# p2c14_001.net
KiCad netlist of a schematic drawn in EAGLE
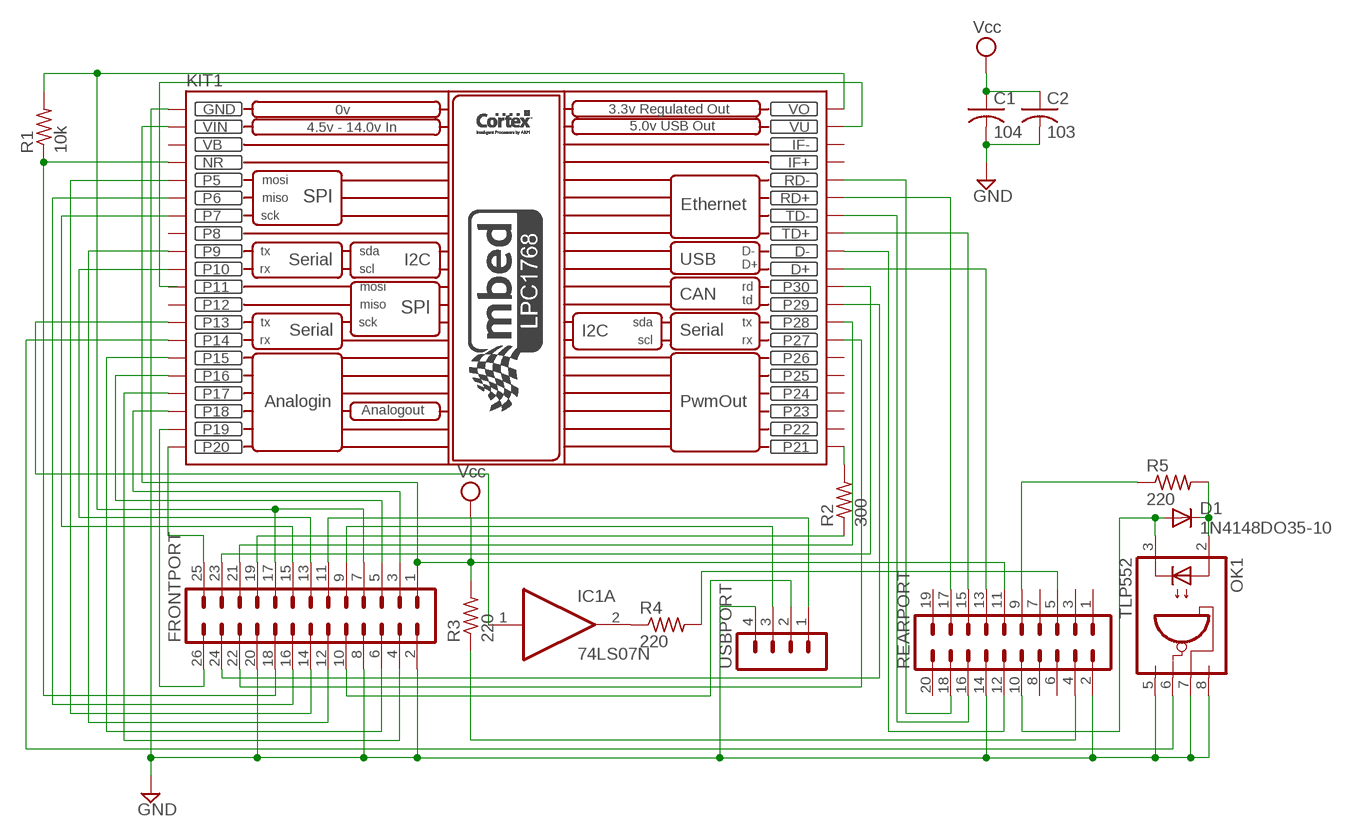
[diagram p0: schematic, sheet 1]

(export (version "E")
  (design (tool "Eeschema 10.0.6"))
  (components
    (comp (ref "C1")
      (value "104")
      (footprint "eagle-import:C025-025X050")
      (libsource (lib "eagle-import") (part "C-US025-025X050"))
    )
    (comp (ref "C2")
      (value "103")
      (footprint "eagle-import:C050-075X075")
      (libsource (lib "eagle-import") (part "C-US050-075X075"))
    )
    (comp (ref "D1")
      (value "1N4148DO35-10")
      (footprint "eagle-import:DO35-10")
      (libsource (lib "eagle-import") (part "1N4148DO35-10"))
    )
    (comp (ref "FRONTPORT")
      (value "ML26L")
      (footprint "eagle-import:ML26L")
      (libsource (lib "eagle-import") (part "ML26L"))
    )
    (comp (ref "IC1")
      (value "74LS07N")
      (footprint "eagle-import:DIL14")
      (libsource (lib "eagle-import") (part "7407NLS"))
    )
    (comp (ref "KIT1")
      (value "MBED_NXP_LPC1768")
      (footprint "eagle-import:MBED-KIT")
      (libsource (lib "eagle-import") (part "MBED_NXP_LPC1768"))
    )
    (comp (ref "OK1")
      (value "TLP552")
      (footprint "eagle-import:DIL08")
      (fields (field (name "MPN") "6N137"))
      (libsource (lib "eagle-import") (part "6N137"))
    )
    (comp (ref "R1")
      (value "10k")
      (footprint "eagle-import:0204_7")
      (libsource (lib "eagle-import") (part "R-US_0204/7"))
    )
    (comp (ref "R2")
      (value "300")
      (footprint "eagle-import:0204_7")
      (libsource (lib "eagle-import") (part "R-US_0204/7"))
    )
    (comp (ref "R3")
      (value "220")
      (footprint "eagle-import:0204_7")
      (libsource (lib "eagle-import") (part "R-US_0204/7"))
    )
    (comp (ref "R4")
      (value "220")
      (footprint "eagle-import:0204_7")
      (libsource (lib "eagle-import") (part "R-US_0204/7"))
    )
    (comp (ref "R5")
      (value "220")
      (footprint "eagle-import:0204_7")
      (libsource (lib "eagle-import") (part "R-US_0204/7"))
    )
    (comp (ref "REARPORT")
      (value "ML20L")
      (footprint "eagle-import:ML20L")
      (libsource (lib "eagle-import") (part "ML20L"))
    )
    (comp (ref "USBPORT")
      (value "MA04-1")
      (footprint "eagle-import:MA04-1")
      (libsource (lib "eagle-import") (part "MA04-1"))
    )
  )
  (nets
    (net (code "1") (name "/VB") (class "Default")
      (node (ref "KIT1") (pin "VB") (pinfunction "VB_VB") (pintype "power_in"))
    )
    (net (code "2") (name "GND") (class "Default")
      (node (ref "C1") (pin "2") (pinfunction "2_2") (pintype "passive"))
      (node (ref "C2") (pin "2") (pinfunction "2_2") (pintype "passive"))
      (node (ref "FRONTPORT") (pin "2") (pinfunction "2_2") (pintype "passive"))
      (node (ref "FRONTPORT") (pin "20") (pinfunction "20_20") (pintype "passive"))
      (node (ref "FRONTPORT") (pin "8") (pinfunction "8_8") (pintype "passive"))
      (node (ref "KIT1") (pin "GND") (pinfunction "GND_GND") (pintype "power_in"))
      (node (ref "OK1") (pin "5") (pinfunction "GND_5") (pintype "passive"))
      (node (ref "OK1") (pin "7") (pinfunction "VE_7") (pintype "passive"))
      (node (ref "OK1") (pin "8") (pinfunction "VCC_8") (pintype "passive"))
      (node (ref "REARPORT") (pin "14") (pinfunction "14_14") (pintype "passive"))
      (node (ref "REARPORT") (pin "2") (pinfunction "2_2") (pintype "passive"))
      (node (ref "USBPORT") (pin "4") (pinfunction "4_4") (pintype "passive"))
    )
    (net (code "3") (name "Net-(FRONTPORT-Pad9)") (class "Default")
      (node (ref "FRONTPORT") (pin "9") (pinfunction "9_9") (pintype "passive"))
      (node (ref "USBPORT") (pin "3") (pinfunction "3_3") (pintype "passive"))
    )
    (net (code "4") (name "Net-(FRONTPORT-Pad10)") (class "Default")
      (node (ref "FRONTPORT") (pin "10") (pinfunction "10_10") (pintype "passive"))
      (node (ref "USBPORT") (pin "2") (pinfunction "2_2") (pintype "passive"))
    )
    (net (code "5") (name "Net-(FRONTPORT-Pad11)") (class "Default")
      (node (ref "FRONTPORT") (pin "11") (pinfunction "11_11") (pintype "passive"))
      (node (ref "USBPORT") (pin "1") (pinfunction "1_1") (pintype "passive"))
    )
    (net (code "6") (name "Net-(FRONTPORT-Pad18)") (class "Default")
      (node (ref "FRONTPORT") (pin "18") (pinfunction "18_18") (pintype "passive"))
      (node (ref "KIT1") (pin "NR") (pinfunction "NR_NR") (pintype "power_in"))
      (node (ref "R1") (pin "1") (pinfunction "1_1") (pintype "passive"))
    )
    (net (code "7") (name "Net-(FRONTPORT-Pad19)") (class "Default")
      (node (ref "FRONTPORT") (pin "19") (pinfunction "19_19") (pintype "passive"))
      (node (ref "R2") (pin "1") (pinfunction "1_1") (pintype "passive"))
    )
    (net (code "8") (name "Net-(IC1A-I)") (class "Default")
      (node (ref "IC1") (pin "1") (pinfunction "I_1") (pintype "input"))
      (node (ref "KIT1") (pin "P$13") (pinfunction "P13_P$13") (pintype "bidirectional"))
    )
    (net (code "9") (name "Net-(IC1A-O)") (class "Default")
      (node (ref "IC1") (pin "2") (pinfunction "O_2") (pintype "open_collector"))
      (node (ref "R4") (pin "1") (pinfunction "1_1") (pintype "passive"))
    )
    (net (code "10") (name "Net-(KIT1-P5)") (class "Default")
      (node (ref "FRONTPORT") (pin "14") (pinfunction "14_14") (pintype "passive"))
      (node (ref "KIT1") (pin "P$5") (pinfunction "P5_P$5") (pintype "bidirectional"))
    )
    (net (code "11") (name "Net-(KIT1-P6)") (class "Default")
      (node (ref "FRONTPORT") (pin "16") (pinfunction "16_16") (pintype "passive"))
      (node (ref "KIT1") (pin "P$6") (pinfunction "P6_P$6") (pintype "bidirectional"))
    )
    (net (code "12") (name "Net-(KIT1-P7)") (class "Default")
      (node (ref "FRONTPORT") (pin "15") (pinfunction "15_15") (pintype "passive"))
      (node (ref "KIT1") (pin "P$7") (pinfunction "P7_P$7") (pintype "bidirectional"))
    )
    (net (code "13") (name "Net-(KIT1-P9)") (class "Default")
      (node (ref "FRONTPORT") (pin "12") (pinfunction "12_12") (pintype "passive"))
      (node (ref "KIT1") (pin "P$9") (pinfunction "P9_P$9") (pintype "bidirectional"))
    )
    (net (code "14") (name "Net-(KIT1-P10)") (class "Default")
      (node (ref "FRONTPORT") (pin "13") (pinfunction "13_13") (pintype "passive"))
      (node (ref "KIT1") (pin "P$10") (pinfunction "P10_P$10") (pintype "bidirectional"))
    )
    (net (code "15") (name "Net-(KIT1-P14)") (class "Default")
      (node (ref "KIT1") (pin "P$14") (pinfunction "P14_P$14") (pintype "bidirectional"))
      (node (ref "OK1") (pin "6") (pinfunction "VO_6") (pintype "passive"))
    )
    (net (code "16") (name "Net-(KIT1-P15)") (class "Default")
      (node (ref "FRONTPORT") (pin "6") (pinfunction "6_6") (pintype "passive"))
      (node (ref "KIT1") (pin "P$15") (pinfunction "P15_P$15") (pintype "bidirectional"))
    )
    (net (code "17") (name "Net-(KIT1-P16)") (class "Default")
      (node (ref "FRONTPORT") (pin "5") (pinfunction "5_5") (pintype "passive"))
      (node (ref "KIT1") (pin "P$16") (pinfunction "P16_P$16") (pintype "bidirectional"))
    )
    (net (code "18") (name "Net-(KIT1-P17)") (class "Default")
      (node (ref "FRONTPORT") (pin "4") (pinfunction "4_4") (pintype "passive"))
      (node (ref "KIT1") (pin "P$17") (pinfunction "P17_P$17") (pintype "bidirectional"))
    )
    (net (code "19") (name "Net-(KIT1-P18)") (class "Default")
      (node (ref "FRONTPORT") (pin "3") (pinfunction "3_3") (pintype "passive"))
      (node (ref "KIT1") (pin "P$18") (pinfunction "P18_P$18") (pintype "bidirectional"))
    )
    (net (code "20") (name "Net-(KIT1-P19)") (class "Default")
      (node (ref "FRONTPORT") (pin "26") (pinfunction "26_26") (pintype "passive"))
      (node (ref "KIT1") (pin "P$19") (pinfunction "P19_P$19") (pintype "bidirectional"))
    )
    (net (code "21") (name "Net-(KIT1-P20)") (class "Default")
      (node (ref "FRONTPORT") (pin "25") (pinfunction "25_25") (pintype "passive"))
      (node (ref "KIT1") (pin "P$20") (pinfunction "P20_P$20") (pintype "bidirectional"))
    )
    (net (code "22") (name "Net-(KIT1-P21)") (class "Default")
      (node (ref "KIT1") (pin "P$21") (pinfunction "P21_P$21") (pintype "bidirectional"))
      (node (ref "R2") (pin "2") (pinfunction "2_2") (pintype "passive"))
    )
    (net (code "23") (name "Net-(KIT1-P27)") (class "Default")
      (node (ref "FRONTPORT") (pin "22") (pinfunction "22_22") (pintype "passive"))
      (node (ref "KIT1") (pin "P$27") (pinfunction "P27_P$27") (pintype "bidirectional"))
    )
    (net (code "24") (name "Net-(KIT1-P28)") (class "Default")
      (node (ref "FRONTPORT") (pin "21") (pinfunction "21_21") (pintype "passive"))
      (node (ref "KIT1") (pin "P$28") (pinfunction "P28_P$28") (pintype "bidirectional"))
    )
    (net (code "25") (name "Net-(KIT1-P29)") (class "Default")
      (node (ref "FRONTPORT") (pin "24") (pinfunction "24_24") (pintype "passive"))
      (node (ref "KIT1") (pin "P$29") (pinfunction "P29_P$29") (pintype "bidirectional"))
    )
    (net (code "26") (name "Net-(KIT1-P30)") (class "Default")
      (node (ref "FRONTPORT") (pin "23") (pinfunction "23_23") (pintype "passive"))
      (node (ref "KIT1") (pin "P$30") (pinfunction "P30_P$30") (pintype "bidirectional"))
    )
    (net (code "27") (name "Net-(KIT1-PadD+)") (class "Default")
      (node (ref "KIT1") (pin "D+") (pinfunction "D+_D+") (pintype "bidirectional"))
      (node (ref "REARPORT") (pin "13") (pinfunction "13_13") (pintype "passive"))
    )
    (net (code "28") (name "Net-(KIT1-PadD-)") (class "Default")
      (node (ref "KIT1") (pin "D-") (pinfunction "D-_D-") (pintype "bidirectional"))
      (node (ref "REARPORT") (pin "12") (pinfunction "12_12") (pintype "passive"))
    )
    (net (code "29") (name "Net-(KIT1-PadRD+)") (class "Default")
      (node (ref "KIT1") (pin "RD+") (pinfunction "RD+_RD+") (pintype "bidirectional"))
      (node (ref "REARPORT") (pin "17") (pinfunction "17_17") (pintype "passive"))
    )
    (net (code "30") (name "Net-(KIT1-PadRD-)") (class "Default")
      (node (ref "KIT1") (pin "RD-") (pinfunction "RD-_RD-") (pintype "bidirectional"))
      (node (ref "REARPORT") (pin "18") (pinfunction "18_18") (pintype "passive"))
    )
    (net (code "31") (name "Net-(KIT1-PadTD+)") (class "Default")
      (node (ref "KIT1") (pin "TD+") (pinfunction "TD+_TD+") (pintype "bidirectional"))
      (node (ref "REARPORT") (pin "15") (pinfunction "15_15") (pintype "passive"))
    )
    (net (code "32") (name "Net-(KIT1-PadTD-)") (class "Default")
      (node (ref "KIT1") (pin "TD-") (pinfunction "TD-_TD-") (pintype "bidirectional"))
      (node (ref "REARPORT") (pin "16") (pinfunction "16_16") (pintype "passive"))
    )
    (net (code "33") (name "Net-(KIT1-VO)") (class "Default")
      (node (ref "FRONTPORT") (pin "17") (pinfunction "17_17") (pintype "passive"))
      (node (ref "FRONTPORT") (pin "7") (pinfunction "7_7") (pintype "passive"))
      (node (ref "KIT1") (pin "VOUT") (pinfunction "VO_VOUT") (pintype "power_in"))
      (node (ref "R1") (pin "2") (pinfunction "2_2") (pintype "passive"))
    )
    (net (code "34") (name "Net-(OK1-A)") (class "Default")
      (node (ref "D1") (pin "C") (pinfunction "C_C") (pintype "passive"))
      (node (ref "OK1") (pin "2") (pinfunction "A_2") (pintype "passive"))
      (node (ref "R5") (pin "2") (pinfunction "2_2") (pintype "passive"))
    )
    (net (code "35") (name "Net-(OK1-C)") (class "Default")
      (node (ref "D1") (pin "A") (pinfunction "A_A") (pintype "passive"))
      (node (ref "OK1") (pin "3") (pinfunction "C_3") (pintype "passive"))
      (node (ref "REARPORT") (pin "10") (pinfunction "10_10") (pintype "passive"))
    )
    (net (code "36") (name "Net-(R3-Pad1)") (class "Default")
      (node (ref "R3") (pin "1") (pinfunction "1_1") (pintype "passive"))
      (node (ref "REARPORT") (pin "4") (pinfunction "4_4") (pintype "passive"))
    )
    (net (code "37") (name "Net-(R4-Pad2)") (class "Default")
      (node (ref "R4") (pin "2") (pinfunction "2_2") (pintype "passive"))
      (node (ref "REARPORT") (pin "5") (pinfunction "5_5") (pintype "passive"))
    )
    (net (code "38") (name "Net-(R5-Pad1)") (class "Default")
      (node (ref "R5") (pin "1") (pinfunction "1_1") (pintype "passive"))
      (node (ref "REARPORT") (pin "9") (pinfunction "9_9") (pintype "passive"))
    )
    (net (code "39") (name "Vcc") (class "Default")
      (node (ref "C1") (pin "1") (pinfunction "1_1") (pintype "passive"))
      (node (ref "C2") (pin "1") (pinfunction "1_1") (pintype "passive"))
      (node (ref "FRONTPORT") (pin "1") (pinfunction "1_1") (pintype "passive"))
      (node (ref "KIT1") (pin "VIN") (pinfunction "VIN_VIN") (pintype "power_in"))
      (node (ref "R3") (pin "2") (pinfunction "2_2") (pintype "passive"))
      (node (ref "REARPORT") (pin "11") (pinfunction "11_11") (pintype "passive"))
    )
    (net (code "40") (name "unconnected-(KIT1-P8-PadP$8)") (class "Default")
      (node (ref "KIT1") (pin "P$8") (pinfunction "P8_P$8") (pintype "bidirectional"))
    )
    (net (code "41") (name "unconnected-(KIT1-P11-PadP$11)") (class "Default")
      (node (ref "KIT1") (pin "P$11") (pinfunction "P11_P$11") (pintype "bidirectional"))
    )
    (net (code "42") (name "unconnected-(KIT1-P12-PadP$12)") (class "Default")
      (node (ref "KIT1") (pin "P$12") (pinfunction "P12_P$12") (pintype "bidirectional"))
    )
    (net (code "43") (name "unconnected-(KIT1-P22-PadP$22)") (class "Default")
      (node (ref "KIT1") (pin "P$22") (pinfunction "P22_P$22") (pintype "bidirectional"))
    )
    (net (code "44") (name "unconnected-(KIT1-P23-PadP$23)") (class "Default")
      (node (ref "KIT1") (pin "P$23") (pinfunction "P23_P$23") (pintype "bidirectional"))
    )
    (net (code "45") (name "unconnected-(KIT1-P24-PadP$24)") (class "Default")
      (node (ref "KIT1") (pin "P$24") (pinfunction "P24_P$24") (pintype "bidirectional"))
    )
    (net (code "46") (name "unconnected-(KIT1-P25-PadP$25)") (class "Default")
      (node (ref "KIT1") (pin "P$25") (pinfunction "P25_P$25") (pintype "bidirectional"))
    )
    (net (code "47") (name "unconnected-(KIT1-P26-PadP$26)") (class "Default")
      (node (ref "KIT1") (pin "P$26") (pinfunction "P26_P$26") (pintype "bidirectional"))
    )
    (net (code "48") (name "unconnected-(KIT1-PadIF+)") (class "Default")
      (node (ref "KIT1") (pin "IF+") (pinfunction "IF+_IF+") (pintype "bidirectional"))
    )
    (net (code "49") (name "unconnected-(KIT1-PadIF-)") (class "Default")
      (node (ref "KIT1") (pin "IF-") (pinfunction "IF-_IF-") (pintype "bidirectional"))
    )
    (net (code "50") (name "unconnected-(KIT1-PadVU)") (class "Default")
      (node (ref "KIT1") (pin "VU") (pinfunction "VU_VU") (pintype "power_in"))
    )
    (net (code "51") (name "unconnected-(REARPORT-Pad1)") (class "Default")
      (node (ref "REARPORT") (pin "1") (pinfunction "1_1") (pintype "passive"))
    )
    (net (code "52") (name "unconnected-(REARPORT-Pad3)") (class "Default")
      (node (ref "REARPORT") (pin "3") (pinfunction "3_3") (pintype "passive"))
    )
    (net (code "53") (name "unconnected-(REARPORT-Pad6)") (class "Default")
      (node (ref "REARPORT") (pin "6") (pinfunction "6_6") (pintype "passive"))
    )
    (net (code "54") (name "unconnected-(REARPORT-Pad7)") (class "Default")
      (node (ref "REARPORT") (pin "7") (pinfunction "7_7") (pintype "passive"))
    )
    (net (code "55") (name "unconnected-(REARPORT-Pad8)") (class "Default")
      (node (ref "REARPORT") (pin "8") (pinfunction "8_8") (pintype "passive"))
    )
    (net (code "56") (name "unconnected-(REARPORT-Pad19)") (class "Default")
      (node (ref "REARPORT") (pin "19") (pinfunction "19_19") (pintype "passive"))
    )
    (net (code "57") (name "unconnected-(REARPORT-Pad20)") (class "Default")
      (node (ref "REARPORT") (pin "20") (pinfunction "20_20") (pintype "passive"))
    )
  )
)
